# AnalogMuxingTing.net
KiCad netlist of a schematic drawn in Altium Designer
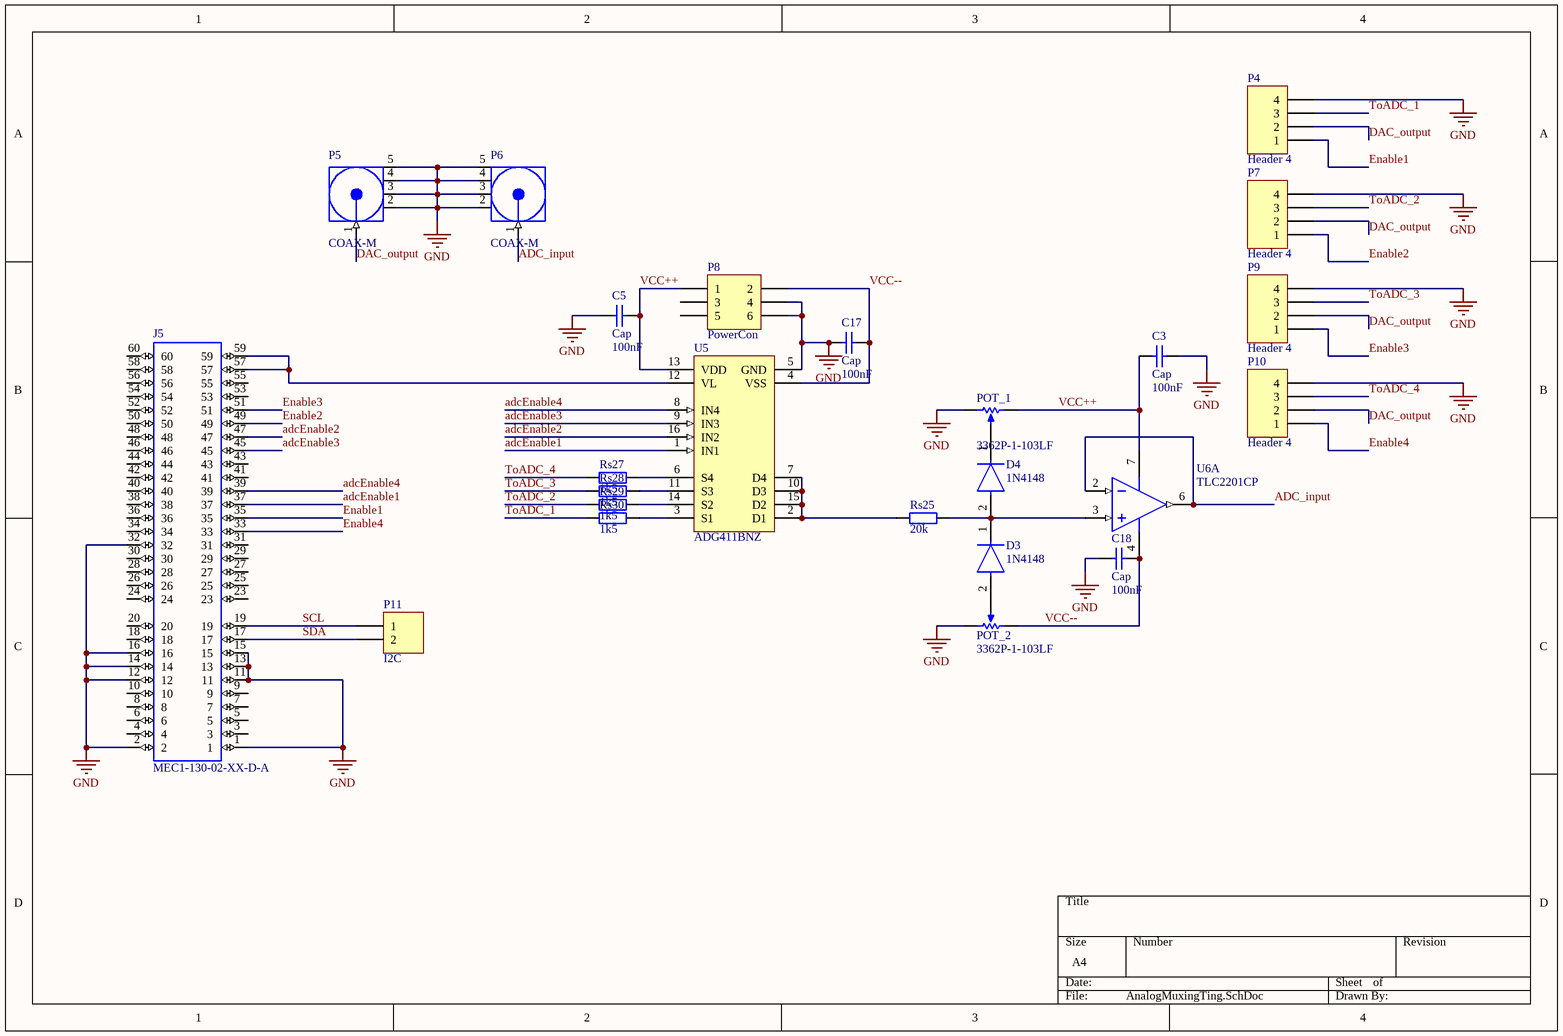
[diagram p0: AnalogMuxingTing.SchDoc]

(export (version "E")
  (design (tool "Eeschema 10.0.6"))
  (components
    (comp (ref "C3")
      (value "Cap")
      (footprint "RAD-0.2  PCBK")
      (description "Capacitor")
      (fields (field (name "ALTIUM_VALUE") "100nF") (field (name "PUBLISHER") "Altium Limited"))
      (libsource (lib "pcb_kursus_lib2020") (part "Cap PCBK"))
    )
    (comp (ref "C5")
      (value "Cap")
      (footprint "RAD-0.2  PCBK")
      (description "Capacitor")
      (fields (field (name "ALTIUM_VALUE") "100nF") (field (name "PUBLISHER") "Altium Limited"))
      (libsource (lib "pcb_kursus_lib2020") (part "Cap PCBK"))
    )
    (comp (ref "C17")
      (value "Cap")
      (footprint "RAD-0.2  PCBK")
      (description "Capacitor")
      (fields (field (name "ALTIUM_VALUE") "100nF") (field (name "PUBLISHER") "Altium Limited"))
      (libsource (lib "pcb_kursus_lib2020") (part "Cap PCBK"))
    )
    (comp (ref "C18")
      (value "Cap")
      (footprint "RAD-0.2  PCBK")
      (description "Capacitor")
      (fields (field (name "ALTIUM_VALUE") "100nF") (field (name "PUBLISHER") "Altium Limited"))
      (libsource (lib "pcb_kursus_lib2020") (part "Cap PCBK"))
    )
    (comp (ref "D3")
      (value "1N4148")
      (footprint "FP-017AG-MFG")
      (description "DIODE GEN PURP 100V 200MA DO35")
      (fields (field (name "VOLTAGE") "100V"))
      (libsource (lib "Altium Content Vault") (part "d7152d700b627762746794eb795d46e"))
    )
    (comp (ref "D4")
      (value "1N4148")
      (footprint "FP-017AG-MFG")
      (description "DIODE GEN PURP 100V 200MA DO35")
      (fields (field (name "VOLTAGE") "100V"))
      (libsource (lib "Altium Content Vault") (part "d7152d700b627762746794eb795d46e"))
    )
    (comp (ref "J5")
      (value "MEC1-130-02-XX-D-A")
      (footprint "MEC1-130-02-XX-D-A")
      (description "1MM MINI-EDGE CARD ASSEMBLY.  MANUFACTURER: SAMTEC.")
      (fields (field (name "MF") "Samtec"))
      (libsource (lib "MEC1-130-02-XX-D-A") (part "MEC1-130-02-XX-D-A"))
    )
    (comp (ref "P4")
      (value "Header 4")
      (footprint "HDR1X4")
      (description "Header, 4-Pin")
      (fields (field (name "PUBLISHER") "Altium Limited"))
      (libsource (lib "Miscellaneous Connectors") (part "Header 4"))
    )
    (comp (ref "P5")
      (value "COAX-M")
      (footprint "BNC_B6251C1-NT3G-50 PCBK")
      (description "RF Coaxial PCB Connector, MMCX; Thru-Hole, Vertical Mount Plug,  50 Ohm Impedance")
      (fields (field (name "PUBLISHER") "Altium Limited"))
      (libsource (lib "pcb_kursus_lib2020") (part "BNC PCBK"))
    )
    (comp (ref "P6")
      (value "COAX-M")
      (footprint "BNC_B6251C1-NT3G-50 PCBK")
      (description "RF Coaxial PCB Connector, MMCX; Thru-Hole, Vertical Mount Plug,  50 Ohm Impedance")
      (fields (field (name "PUBLISHER") "Altium Limited"))
      (libsource (lib "pcb_kursus_lib2020") (part "BNC PCBK"))
    )
    (comp (ref "P7")
      (value "Header 4")
      (footprint "HDR1X4")
      (description "Header, 4-Pin")
      (fields (field (name "PUBLISHER") "Altium Limited"))
      (libsource (lib "Miscellaneous Connectors") (part "Header 4"))
    )
    (comp (ref "P8")
      (value "PowerCon")
      (footprint "HDR2X3")
      (description "Header, 3-Pin, Dual row")
      (fields (field (name "PUBLISHER") "Altium Limited"))
      (libsource (lib "Miscellaneous Connectors") (part "Header 3X2"))
    )
    (comp (ref "P9")
      (value "Header 4")
      (footprint "HDR1X4")
      (description "Header, 4-Pin")
      (fields (field (name "PUBLISHER") "Altium Limited"))
      (libsource (lib "Miscellaneous Connectors") (part "Header 4"))
    )
    (comp (ref "P10")
      (value "Header 4")
      (footprint "HDR1X4")
      (description "Header, 4-Pin")
      (fields (field (name "PUBLISHER") "Altium Limited"))
      (libsource (lib "Miscellaneous Connectors") (part "Header 4"))
    )
    (comp (ref "P11")
      (value "I2C")
      (footprint "HDR1X2")
      (description "Header, 2-Pin")
      (fields (field (name "PUBLISHER") "Altium Limited"))
      (libsource (lib "Miscellaneous Connectors") (part "Header 2"))
    )
    (comp (ref "POT_1")
      (value "3362P-1-103LF")
      (footprint "BOUR-3362P")
      (description "Square Trimpot(R) Trimming Potentiometer, 10 KOhm, 300 V, -55 to 125 degC, 3-Pin THD, RoHS, Tube")
      (fields (field (name "TOLERANCE") "1%"))
      (libsource (lib "Altium Content Vault") (part "RES-POT-3"))
    )
    (comp (ref "POT_2")
      (value "3362P-1-103LF")
      (footprint "BOUR-3362P")
      (description "Square Trimpot(R) Trimming Potentiometer, 10 KOhm, 300 V, -55 to 125 degC, 3-Pin THD, RoHS, Tube")
      (fields (field (name "TOLERANCE") "1%"))
      (libsource (lib "Altium Content Vault") (part "RES-POT-3"))
    )
    (comp (ref "Rs25")
      (value "20k")
      (footprint "AXIAL-0.4 PCBK")
      (description "Resistor")
      (fields (field (name "PUBLISHER") "Altium Limited"))
      (libsource (lib "pcb_kursus_lib2020") (part "Res PCBK"))
    )
    (comp (ref "Rs27")
      (value "1k5")
      (footprint "AXIAL-0.4 PCBK")
      (description "Resistor")
      (fields (field (name "PUBLISHER") "Altium Limited"))
      (libsource (lib "pcb_kursus_lib2020") (part "Res PCBK"))
    )
    (comp (ref "Rs28")
      (value "1k5")
      (footprint "AXIAL-0.4 PCBK")
      (description "Resistor")
      (fields (field (name "PUBLISHER") "Altium Limited"))
      (libsource (lib "pcb_kursus_lib2020") (part "Res PCBK"))
    )
    (comp (ref "Rs29")
      (value "1k5")
      (footprint "AXIAL-0.4 PCBK")
      (description "Resistor")
      (fields (field (name "PUBLISHER") "Altium Limited"))
      (libsource (lib "pcb_kursus_lib2020") (part "Res PCBK"))
    )
    (comp (ref "Rs30")
      (value "1k5")
      (footprint "AXIAL-0.4 PCBK")
      (description "Resistor")
      (fields (field (name "PUBLISHER") "Altium Limited"))
      (libsource (lib "pcb_kursus_lib2020") (part "Res PCBK"))
    )
    (comp (ref "U5")
      (value "ADG411BNZ")
      (footprint "ADI-N-16")
      (description "LC2MOS Precision Quad SPST Switches, 25 Ohm Ron, 16-pin DIP (N-16), Tube")
      (fields (field (name "MANUFACTURER") "Analog Devices"))
      (libsource (lib "Altium Content Vault") (part "ADI-ADG411-N-16"))
    )
    (comp (ref "U6")
      (value "TLC2201CP")
      (footprint "P0008A")
      (fields (field (name "MANUFACTURER") "Texas Instruments"))
      (libsource (lib "Altium Content Vault") (part "TI-TLC2201-8"))
    )
  )
  (nets
    (net (code "1") (name "/ADC_input") (class "Default")
      (node (ref "P6") (pin "1") (pinfunction "Signal_1") (pintype "input"))
      (node (ref "U6") (pin "2") (pinfunction "IN-_2") (pintype "input"))
      (node (ref "U6") (pin "6") (pinfunction "OUT_6") (pintype "output"))
    )
    (net (code "2") (name "/DAC_output") (class "Default")
      (node (ref "P10") (pin "2") (pinfunction "2_2") (pintype "passive"))
      (node (ref "P4") (pin "2") (pinfunction "2_2") (pintype "passive"))
      (node (ref "P5") (pin "1") (pinfunction "Signal_1") (pintype "input"))
      (node (ref "P7") (pin "2") (pinfunction "2_2") (pintype "passive"))
      (node (ref "P9") (pin "2") (pinfunction "2_2") (pintype "passive"))
    )
    (net (code "3") (name "/Enable1") (class "Default")
      (node (ref "J5") (pin "35") (pinfunction "35_35") (pintype "bidirectional"))
      (node (ref "P4") (pin "1") (pinfunction "1_1") (pintype "passive"))
    )
    (net (code "4") (name "/Enable2") (class "Default")
      (node (ref "J5") (pin "49") (pinfunction "49_49") (pintype "bidirectional"))
      (node (ref "P7") (pin "1") (pinfunction "1_1") (pintype "passive"))
    )
    (net (code "5") (name "/Enable3") (class "Default")
      (node (ref "J5") (pin "51") (pinfunction "51_51") (pintype "bidirectional"))
      (node (ref "P9") (pin "1") (pinfunction "1_1") (pintype "passive"))
    )
    (net (code "6") (name "/Enable4") (class "Default")
      (node (ref "J5") (pin "33") (pinfunction "33_33") (pintype "bidirectional"))
      (node (ref "P10") (pin "1") (pinfunction "1_1") (pintype "passive"))
    )
    (net (code "7") (name "/SCL") (class "Default")
      (node (ref "J5") (pin "19") (pinfunction "19_19") (pintype "bidirectional"))
      (node (ref "P11") (pin "1") (pinfunction "1_1") (pintype "passive"))
    )
    (net (code "8") (name "/SDA") (class "Default")
      (node (ref "J5") (pin "17") (pinfunction "17_17") (pintype "bidirectional"))
      (node (ref "P11") (pin "2") (pinfunction "2_2") (pintype "passive"))
    )
    (net (code "9") (name "/ToADC_1") (class "Default")
      (node (ref "P4") (pin "3") (pinfunction "3_3") (pintype "passive"))
      (node (ref "Rs30") (pin "2") (pinfunction "2_2") (pintype "passive"))
    )
    (net (code "10") (name "/ToADC_2") (class "Default")
      (node (ref "P7") (pin "3") (pinfunction "3_3") (pintype "passive"))
      (node (ref "Rs29") (pin "2") (pinfunction "2_2") (pintype "passive"))
    )
    (net (code "11") (name "/ToADC_3") (class "Default")
      (node (ref "P9") (pin "3") (pinfunction "3_3") (pintype "passive"))
      (node (ref "Rs28") (pin "2") (pinfunction "2_2") (pintype "passive"))
    )
    (net (code "12") (name "/ToADC_4") (class "Default")
      (node (ref "P10") (pin "3") (pinfunction "3_3") (pintype "passive"))
      (node (ref "Rs27") (pin "2") (pinfunction "2_2") (pintype "passive"))
    )
    (net (code "13") (name "/VCC++") (class "Default")
      (node (ref "C3") (pin "2") (pinfunction "2_2") (pintype "passive"))
      (node (ref "C5") (pin "1") (pinfunction "1_1") (pintype "passive"))
      (node (ref "P8") (pin "1") (pinfunction "1_1") (pintype "passive"))
      (node (ref "POT_1") (pin "3") (pinfunction "CW_3") (pintype "passive"))
      (node (ref "U5") (pin "13") (pinfunction "VDD_13") (pintype "power_in"))
      (node (ref "U6") (pin "7") (pinfunction "VDD+_7") (pintype "power_in"))
    )
    (net (code "14") (name "/VCC--") (class "Default")
      (node (ref "C17") (pin "2") (pinfunction "2_2") (pintype "passive"))
      (node (ref "C18") (pin "2") (pinfunction "2_2") (pintype "passive"))
      (node (ref "P8") (pin "2") (pinfunction "2_2") (pintype "passive"))
      (node (ref "POT_2") (pin "1") (pinfunction "CCW_1") (pintype "passive"))
      (node (ref "U5") (pin "4") (pinfunction "VSS_4") (pintype "power_in"))
      (node (ref "U6") (pin "4") (pinfunction "VDD-/GND_4") (pintype "power_in"))
    )
    (net (code "15") (name "/adcEnable1") (class "Default")
      (node (ref "J5") (pin "37") (pinfunction "37_37") (pintype "bidirectional"))
      (node (ref "U5") (pin "1") (pinfunction "IN1_1") (pintype "input"))
    )
    (net (code "16") (name "/adcEnable2") (class "Default")
      (node (ref "J5") (pin "47") (pinfunction "47_47") (pintype "bidirectional"))
      (node (ref "U5") (pin "16") (pinfunction "IN2_16") (pintype "input"))
    )
    (net (code "17") (name "/adcEnable3") (class "Default")
      (node (ref "J5") (pin "45") (pinfunction "45_45") (pintype "bidirectional"))
      (node (ref "U5") (pin "9") (pinfunction "IN3_9") (pintype "input"))
    )
    (net (code "18") (name "/adcEnable4") (class "Default")
      (node (ref "J5") (pin "39") (pinfunction "39_39") (pintype "bidirectional"))
      (node (ref "U5") (pin "8") (pinfunction "IN4_8") (pintype "input"))
    )
    (net (code "19") (name "GND") (class "Default")
      (node (ref "C17") (pin "1") (pinfunction "1_1") (pintype "passive"))
      (node (ref "C18") (pin "1") (pinfunction "1_1") (pintype "passive"))
      (node (ref "C3") (pin "1") (pinfunction "1_1") (pintype "passive"))
      (node (ref "C5") (pin "2") (pinfunction "2_2") (pintype "passive"))
      (node (ref "J5") (pin "1") (pinfunction "1_1") (pintype "bidirectional"))
      (node (ref "J5") (pin "11") (pinfunction "11_11") (pintype "bidirectional"))
      (node (ref "J5") (pin "12") (pinfunction "12_12") (pintype "bidirectional"))
      (node (ref "J5") (pin "13") (pinfunction "13_13") (pintype "bidirectional"))
      (node (ref "J5") (pin "14") (pinfunction "14_14") (pintype "bidirectional"))
      (node (ref "J5") (pin "15") (pinfunction "15_15") (pintype "bidirectional"))
      (node (ref "J5") (pin "16") (pinfunction "16_16") (pintype "bidirectional"))
      (node (ref "J5") (pin "2") (pinfunction "2_2") (pintype "bidirectional"))
      (node (ref "J5") (pin "32") (pinfunction "32_32") (pintype "bidirectional"))
      (node (ref "P10") (pin "4") (pinfunction "4_4") (pintype "passive"))
      (node (ref "P4") (pin "4") (pinfunction "4_4") (pintype "passive"))
      (node (ref "P5") (pin "2") (pinfunction "GND_2") (pintype "power_in"))
      (node (ref "P5") (pin "3") (pinfunction "GND_3") (pintype "power_in"))
      (node (ref "P5") (pin "4") (pinfunction "GND_4") (pintype "power_in"))
      (node (ref "P5") (pin "5") (pinfunction "GND_5") (pintype "power_in"))
      (node (ref "P6") (pin "2") (pinfunction "GND_2") (pintype "power_in"))
      (node (ref "P6") (pin "3") (pinfunction "GND_3") (pintype "power_in"))
      (node (ref "P6") (pin "4") (pinfunction "GND_4") (pintype "power_in"))
      (node (ref "P6") (pin "5") (pinfunction "GND_5") (pintype "power_in"))
      (node (ref "P7") (pin "4") (pinfunction "4_4") (pintype "passive"))
      (node (ref "P8") (pin "4") (pinfunction "4_4") (pintype "passive"))
      (node (ref "P8") (pin "6") (pinfunction "6_6") (pintype "passive"))
      (node (ref "P9") (pin "4") (pinfunction "4_4") (pintype "passive"))
      (node (ref "POT_1") (pin "1") (pinfunction "CCW_1") (pintype "passive"))
      (node (ref "POT_2") (pin "3") (pinfunction "CW_3") (pintype "passive"))
      (node (ref "U5") (pin "5") (pinfunction "GND_5") (pintype "power_in"))
    )
    (net (code "20") (name "Net-(D3-A)") (class "Default")
      (node (ref "D3") (pin "2") (pinfunction "A_2") (pintype "passive"))
      (node (ref "POT_2") (pin "2") (pinfunction "S_2") (pintype "passive"))
    )
    (net (code "21") (name "Net-(D3-C)") (class "Default")
      (node (ref "D3") (pin "1") (pinfunction "C_1") (pintype "passive"))
      (node (ref "D4") (pin "2") (pinfunction "A_2") (pintype "passive"))
      (node (ref "Rs25") (pin "1") (pinfunction "1_1") (pintype "passive"))
      (node (ref "U6") (pin "3") (pinfunction "IN+_3") (pintype "input"))
    )
    (net (code "22") (name "Net-(D4-C)") (class "Default")
      (node (ref "D4") (pin "1") (pinfunction "C_1") (pintype "passive"))
      (node (ref "POT_1") (pin "2") (pinfunction "S_2") (pintype "passive"))
    )
    (net (code "23") (name "Net-(U5-D1)") (class "Default")
      (node (ref "Rs25") (pin "2") (pinfunction "2_2") (pintype "passive"))
      (node (ref "U5") (pin "10") (pinfunction "D3_10") (pintype "passive"))
      (node (ref "U5") (pin "15") (pinfunction "D2_15") (pintype "passive"))
      (node (ref "U5") (pin "2") (pinfunction "D1_2") (pintype "passive"))
      (node (ref "U5") (pin "7") (pinfunction "D4_7") (pintype "passive"))
    )
    (net (code "24") (name "Net-(U5-S1)") (class "Default")
      (node (ref "Rs30") (pin "1") (pinfunction "1_1") (pintype "passive"))
      (node (ref "U5") (pin "3") (pinfunction "S1_3") (pintype "passive"))
    )
    (net (code "25") (name "Net-(U5-S2)") (class "Default")
      (node (ref "Rs29") (pin "1") (pinfunction "1_1") (pintype "passive"))
      (node (ref "U5") (pin "14") (pinfunction "S2_14") (pintype "passive"))
    )
    (net (code "26") (name "Net-(U5-S3)") (class "Default")
      (node (ref "Rs28") (pin "1") (pinfunction "1_1") (pintype "passive"))
      (node (ref "U5") (pin "11") (pinfunction "S3_11") (pintype "passive"))
    )
    (net (code "27") (name "Net-(U5-S4)") (class "Default")
      (node (ref "Rs27") (pin "1") (pinfunction "1_1") (pintype "passive"))
      (node (ref "U5") (pin "6") (pinfunction "S4_6") (pintype "passive"))
    )
    (net (code "28") (name "Net-(U5-VL)") (class "Default")
      (node (ref "J5") (pin "57") (pinfunction "57_57") (pintype "bidirectional"))
      (node (ref "J5") (pin "59") (pinfunction "59_59") (pintype "bidirectional"))
      (node (ref "U5") (pin "12") (pinfunction "VL_12") (pintype "power_in"))
    )
    (net (code "29") (name "unconnected-(J5-Pad3)") (class "Default")
      (node (ref "J5") (pin "3") (pinfunction "3_3") (pintype "bidirectional"))
    )
    (net (code "30") (name "unconnected-(J5-Pad4)") (class "Default")
      (node (ref "J5") (pin "4") (pinfunction "4_4") (pintype "bidirectional"))
    )
    (net (code "31") (name "unconnected-(J5-Pad5)") (class "Default")
      (node (ref "J5") (pin "5") (pinfunction "5_5") (pintype "bidirectional"))
    )
    (net (code "32") (name "unconnected-(J5-Pad6)") (class "Default")
      (node (ref "J5") (pin "6") (pinfunction "6_6") (pintype "bidirectional"))
    )
    (net (code "33") (name "unconnected-(J5-Pad7)") (class "Default")
      (node (ref "J5") (pin "7") (pinfunction "7_7") (pintype "bidirectional"))
    )
    (net (code "34") (name "unconnected-(J5-Pad8)") (class "Default")
      (node (ref "J5") (pin "8") (pinfunction "8_8") (pintype "bidirectional"))
    )
    (net (code "35") (name "unconnected-(J5-Pad9)") (class "Default")
      (node (ref "J5") (pin "9") (pinfunction "9_9") (pintype "bidirectional"))
    )
    (net (code "36") (name "unconnected-(J5-Pad10)") (class "Default")
      (node (ref "J5") (pin "10") (pinfunction "10_10") (pintype "bidirectional"))
    )
    (net (code "37") (name "unconnected-(J5-Pad18)") (class "Default")
      (node (ref "J5") (pin "18") (pinfunction "18_18") (pintype "bidirectional"))
    )
    (net (code "38") (name "unconnected-(J5-Pad20)") (class "Default")
      (node (ref "J5") (pin "20") (pinfunction "20_20") (pintype "bidirectional"))
    )
    (net (code "39") (name "unconnected-(J5-Pad23)") (class "Default")
      (node (ref "J5") (pin "23") (pinfunction "23_23") (pintype "bidirectional"))
    )
    (net (code "40") (name "unconnected-(J5-Pad24)") (class "Default")
      (node (ref "J5") (pin "24") (pinfunction "24_24") (pintype "bidirectional"))
    )
    (net (code "41") (name "unconnected-(J5-Pad25)") (class "Default")
      (node (ref "J5") (pin "25") (pinfunction "25_25") (pintype "bidirectional"))
    )
    (net (code "42") (name "unconnected-(J5-Pad26)") (class "Default")
      (node (ref "J5") (pin "26") (pinfunction "26_26") (pintype "bidirectional"))
    )
    (net (code "43") (name "unconnected-(J5-Pad27)") (class "Default")
      (node (ref "J5") (pin "27") (pinfunction "27_27") (pintype "bidirectional"))
    )
    (net (code "44") (name "unconnected-(J5-Pad28)") (class "Default")
      (node (ref "J5") (pin "28") (pinfunction "28_28") (pintype "bidirectional"))
    )
    (net (code "45") (name "unconnected-(J5-Pad29)") (class "Default")
      (node (ref "J5") (pin "29") (pinfunction "29_29") (pintype "bidirectional"))
    )
    (net (code "46") (name "unconnected-(J5-Pad30)") (class "Default")
      (node (ref "J5") (pin "30") (pinfunction "30_30") (pintype "bidirectional"))
    )
    (net (code "47") (name "unconnected-(J5-Pad31)") (class "Default")
      (node (ref "J5") (pin "31") (pinfunction "31_31") (pintype "bidirectional"))
    )
    (net (code "48") (name "unconnected-(J5-Pad34)") (class "Default")
      (node (ref "J5") (pin "34") (pinfunction "34_34") (pintype "bidirectional"))
    )
    (net (code "49") (name "unconnected-(J5-Pad36)") (class "Default")
      (node (ref "J5") (pin "36") (pinfunction "36_36") (pintype "bidirectional"))
    )
    (net (code "50") (name "unconnected-(J5-Pad38)") (class "Default")
      (node (ref "J5") (pin "38") (pinfunction "38_38") (pintype "bidirectional"))
    )
    (net (code "51") (name "unconnected-(J5-Pad40)") (class "Default")
      (node (ref "J5") (pin "40") (pinfunction "40_40") (pintype "bidirectional"))
    )
    (net (code "52") (name "unconnected-(J5-Pad41)") (class "Default")
      (node (ref "J5") (pin "41") (pinfunction "41_41") (pintype "bidirectional"))
    )
    (net (code "53") (name "unconnected-(J5-Pad42)") (class "Default")
      (node (ref "J5") (pin "42") (pinfunction "42_42") (pintype "bidirectional"))
    )
    (net (code "54") (name "unconnected-(J5-Pad43)") (class "Default")
      (node (ref "J5") (pin "43") (pinfunction "43_43") (pintype "bidirectional"))
    )
    (net (code "55") (name "unconnected-(J5-Pad44)") (class "Default")
      (node (ref "J5") (pin "44") (pinfunction "44_44") (pintype "bidirectional"))
    )
    (net (code "56") (name "unconnected-(J5-Pad46)") (class "Default")
      (node (ref "J5") (pin "46") (pinfunction "46_46") (pintype "bidirectional"))
    )
    (net (code "57") (name "unconnected-(J5-Pad48)") (class "Default")
      (node (ref "J5") (pin "48") (pinfunction "48_48") (pintype "bidirectional"))
    )
    (net (code "58") (name "unconnected-(J5-Pad50)") (class "Default")
      (node (ref "J5") (pin "50") (pinfunction "50_50") (pintype "bidirectional"))
    )
    (net (code "59") (name "unconnected-(J5-Pad52)") (class "Default")
      (node (ref "J5") (pin "52") (pinfunction "52_52") (pintype "bidirectional"))
    )
    (net (code "60") (name "unconnected-(J5-Pad53)") (class "Default")
      (node (ref "J5") (pin "53") (pinfunction "53_53") (pintype "bidirectional"))
    )
    (net (code "61") (name "unconnected-(J5-Pad54)") (class "Default")
      (node (ref "J5") (pin "54") (pinfunction "54_54") (pintype "bidirectional"))
    )
    (net (code "62") (name "unconnected-(J5-Pad55)") (class "Default")
      (node (ref "J5") (pin "55") (pinfunction "55_55") (pintype "bidirectional"))
    )
    (net (code "63") (name "unconnected-(J5-Pad56)") (class "Default")
      (node (ref "J5") (pin "56") (pinfunction "56_56") (pintype "bidirectional"))
    )
    (net (code "64") (name "unconnected-(J5-Pad58)") (class "Default")
      (node (ref "J5") (pin "58") (pinfunction "58_58") (pintype "bidirectional"))
    )
    (net (code "65") (name "unconnected-(J5-Pad60)") (class "Default")
      (node (ref "J5") (pin "60") (pinfunction "60_60") (pintype "bidirectional"))
    )
    (net (code "66") (name "unconnected-(P8-Pad3)") (class "Default")
      (node (ref "P8") (pin "3") (pinfunction "3_3") (pintype "passive"))
    )
    (net (code "67") (name "unconnected-(P8-Pad5)") (class "Default")
      (node (ref "P8") (pin "5") (pinfunction "5_5") (pintype "passive"))
    )
  )
)
